# Bus.net
KiCad netlist of a schematic drawn in Altium Designer
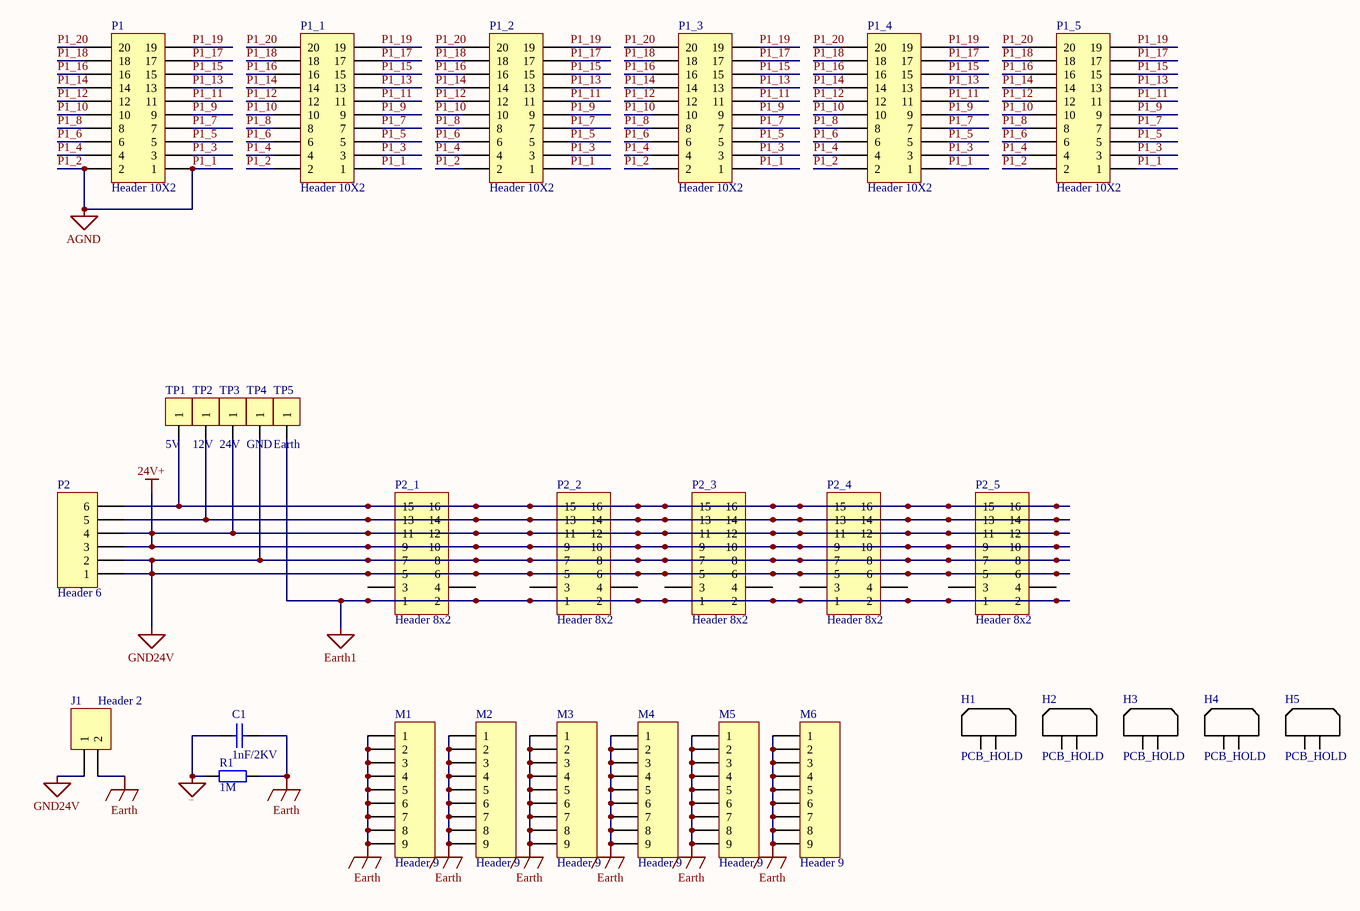
[diagram p0: Bus.SchDoc]

(export (version "E")
  (design (tool "Eeschema 10.0.6"))
  (components
    (comp (ref "C1")
      (value "1nF/2KV")
      (footprint "1206_C")
      (description "Capacitor")
      (libsource (lib "Miscellaneous Devices LC") (part "CC"))
    )
    (comp (ref "H1")
      (value "PCB_HOLD")
      (footprint "PCB_HOLD")
      (fields (field (name "PUBLISHER") "Altium Limited"))
      (libsource (lib "PCB_Project1") (part "PCB_HOLD"))
    )
    (comp (ref "H2")
      (value "PCB_HOLD")
      (footprint "PCB_HOLD")
      (fields (field (name "PUBLISHER") "Altium Limited"))
      (libsource (lib "PCB_Project1") (part "PCB_HOLD"))
    )
    (comp (ref "H3")
      (value "PCB_HOLD")
      (footprint "PCB_HOLD")
      (fields (field (name "PUBLISHER") "Altium Limited"))
      (libsource (lib "PCB_Project1") (part "PCB_HOLD"))
    )
    (comp (ref "H4")
      (value "PCB_HOLD")
      (footprint "PCB_HOLD")
      (fields (field (name "PUBLISHER") "Altium Limited"))
      (libsource (lib "PCB_Project1") (part "PCB_HOLD"))
    )
    (comp (ref "H5")
      (value "PCB_HOLD")
      (footprint "PCB_HOLD")
      (fields (field (name "PUBLISHER") "Altium Limited"))
      (libsource (lib "PCB_Project1") (part "PCB_HOLD"))
    )
    (comp (ref "J1")
      (value "Header 2")
      (footprint "HDR1X2")
      (description "Header, 2-Pin")
      (fields (field (name "PUBLISHER") "Altium Limited"))
      (libsource (lib "Miscellaneous Connectors") (part "Header 2"))
    )
    (comp (ref "M1")
      (value "Header 9")
      (footprint "LK")
      (description "Header, 9-Pin")
      (fields (field (name "PUBLISHER") "Altium Limited"))
      (libsource (lib "Miscellaneous Connectors") (part "Header 9"))
    )
    (comp (ref "M2")
      (value "Header 9")
      (footprint "LK")
      (description "Header, 9-Pin")
      (fields (field (name "PUBLISHER") "Altium Limited"))
      (libsource (lib "Miscellaneous Connectors") (part "Header 9"))
    )
    (comp (ref "M3")
      (value "Header 9")
      (footprint "LK")
      (description "Header, 9-Pin")
      (fields (field (name "PUBLISHER") "Altium Limited"))
      (libsource (lib "Miscellaneous Connectors") (part "Header 9"))
    )
    (comp (ref "M4")
      (value "Header 9")
      (footprint "LK")
      (description "Header, 9-Pin")
      (fields (field (name "PUBLISHER") "Altium Limited"))
      (libsource (lib "Miscellaneous Connectors") (part "Header 9"))
    )
    (comp (ref "M5")
      (value "Header 9")
      (footprint "LK")
      (description "Header, 9-Pin")
      (fields (field (name "PUBLISHER") "Altium Limited"))
      (libsource (lib "Miscellaneous Connectors") (part "Header 9"))
    )
    (comp (ref "M6")
      (value "Header 9")
      (footprint "LK")
      (description "Header, 9-Pin")
      (fields (field (name "PUBLISHER") "Altium Limited"))
      (libsource (lib "Miscellaneous Connectors") (part "Header 9"))
    )
    (comp (ref "P1")
      (value "Header 10X2")
      (footprint "HDR2X10")
      (description "Header, 10-Pin, Dual row")
      (fields (field (name "PUBLISHER") "Altium Limited"))
      (libsource (lib "Miscellaneous Connectors") (part "Header 10X2"))
    )
    (comp (ref "P1_1")
      (value "Header 10X2")
      (footprint "HDR2X10")
      (description "Header, 10-Pin, Dual row")
      (fields (field (name "PUBLISHER") "Altium Limited"))
      (libsource (lib "Miscellaneous Connectors") (part "Header 10X2"))
    )
    (comp (ref "P1_2")
      (value "Header 10X2")
      (footprint "HDR2X10")
      (description "Header, 10-Pin, Dual row")
      (fields (field (name "PUBLISHER") "Altium Limited"))
      (libsource (lib "Miscellaneous Connectors") (part "Header 10X2"))
    )
    (comp (ref "P1_3")
      (value "Header 10X2")
      (footprint "HDR2X10")
      (description "Header, 10-Pin, Dual row")
      (fields (field (name "PUBLISHER") "Altium Limited"))
      (libsource (lib "Miscellaneous Connectors") (part "Header 10X2"))
    )
    (comp (ref "P1_4")
      (value "Header 10X2")
      (footprint "HDR2X10")
      (description "Header, 10-Pin, Dual row")
      (fields (field (name "PUBLISHER") "Altium Limited"))
      (libsource (lib "Miscellaneous Connectors") (part "Header 10X2"))
    )
    (comp (ref "P1_5")
      (value "Header 10X2")
      (footprint "HDR2X10")
      (description "Header, 10-Pin, Dual row")
      (fields (field (name "PUBLISHER") "Altium Limited"))
      (libsource (lib "Miscellaneous Connectors") (part "Header 10X2"))
    )
    (comp (ref "P2")
      (value "Header 6")
      (footprint "15EDG-6-R")
      (description "Header, 6-Pin")
      (fields (field (name "PUBLISHER") "Altium Limited"))
      (libsource (lib "Miscellaneous Connectors") (part "Header 6"))
    )
    (comp (ref "P2_1")
      (value "Header 8x2")
      (footprint "HDR2X8")
      (description "Header, 8-Pin, Dual row")
      (fields (field (name "PUBLISHER") "Altium Limited"))
      (libsource (lib "Miscellaneous Connectors") (part "Header 8X2"))
    )
    (comp (ref "P2_2")
      (value "Header 8x2")
      (footprint "HDR2X8")
      (description "Header, 8-Pin, Dual row")
      (fields (field (name "PUBLISHER") "Altium Limited"))
      (libsource (lib "Miscellaneous Connectors") (part "Header 8X2"))
    )
    (comp (ref "P2_3")
      (value "Header 8x2")
      (footprint "HDR2X8")
      (description "Header, 8-Pin, Dual row")
      (fields (field (name "PUBLISHER") "Altium Limited"))
      (libsource (lib "Miscellaneous Connectors") (part "Header 8X2"))
    )
    (comp (ref "P2_4")
      (value "Header 8x2")
      (footprint "HDR2X8")
      (description "Header, 8-Pin, Dual row")
      (fields (field (name "PUBLISHER") "Altium Limited"))
      (libsource (lib "Miscellaneous Connectors") (part "Header 8X2"))
    )
    (comp (ref "P2_5")
      (value "Header 8x2")
      (footprint "HDR2X8")
      (description "Header, 8-Pin, Dual row")
      (fields (field (name "PUBLISHER") "Altium Limited"))
      (libsource (lib "Miscellaneous Connectors") (part "Header 8X2"))
    )
    (comp (ref "R1")
      (value "1M")
      (footprint "1206_R")
      (description "Resistor")
      (fields (field (name "PUBLISHER") "Altium Limited"))
      (libsource (lib "Miscellaneous Devices LC") (part "Res2"))
    )
    (comp (ref "TP1")
      (value "5V")
      (footprint "TP")
      (description "TP")
      (fields (field (name "PUBLISHER") "Altium Limited"))
      (libsource (lib "GW") (part "TP"))
    )
    (comp (ref "TP2")
      (value "12V")
      (footprint "TP")
      (description "TP")
      (fields (field (name "PUBLISHER") "Altium Limited"))
      (libsource (lib "GW") (part "TP"))
    )
    (comp (ref "TP3")
      (value "24V")
      (footprint "TP")
      (description "TP")
      (fields (field (name "PUBLISHER") "Altium Limited"))
      (libsource (lib "GW") (part "TP"))
    )
    (comp (ref "TP4")
      (value "GND")
      (footprint "TP")
      (description "TP")
      (fields (field (name "PUBLISHER") "Altium Limited"))
      (libsource (lib "GW") (part "TP"))
    )
    (comp (ref "TP5")
      (value "Earth")
      (footprint "TP")
      (description "TP")
      (fields (field (name "PUBLISHER") "Altium Limited"))
      (libsource (lib "GW") (part "TP"))
    )
  )
  (nets
    (net (code "1") (name "/P1_3") (class "Default")
      (node (ref "P1") (pin "3") (pinfunction "3_3") (pintype "passive"))
      (node (ref "P1_1") (pin "3") (pinfunction "3_3") (pintype "passive"))
      (node (ref "P1_2") (pin "3") (pinfunction "3_3") (pintype "passive"))
      (node (ref "P1_3") (pin "3") (pinfunction "3_3") (pintype "passive"))
      (node (ref "P1_4") (pin "3") (pinfunction "3_3") (pintype "passive"))
      (node (ref "P1_5") (pin "3") (pinfunction "3_3") (pintype "passive"))
    )
    (net (code "2") (name "/P1_4") (class "Default")
      (node (ref "P1") (pin "4") (pinfunction "4_4") (pintype "passive"))
      (node (ref "P1_1") (pin "4") (pinfunction "4_4") (pintype "passive"))
      (node (ref "P1_2") (pin "4") (pinfunction "4_4") (pintype "passive"))
      (node (ref "P1_3") (pin "4") (pinfunction "4_4") (pintype "passive"))
      (node (ref "P1_4") (pin "4") (pinfunction "4_4") (pintype "passive"))
      (node (ref "P1_5") (pin "4") (pinfunction "4_4") (pintype "passive"))
    )
    (net (code "3") (name "/P1_5") (class "Default")
      (node (ref "P1") (pin "5") (pinfunction "5_5") (pintype "passive"))
      (node (ref "P1_1") (pin "5") (pinfunction "5_5") (pintype "passive"))
      (node (ref "P1_2") (pin "5") (pinfunction "5_5") (pintype "passive"))
      (node (ref "P1_3") (pin "5") (pinfunction "5_5") (pintype "passive"))
      (node (ref "P1_4") (pin "5") (pinfunction "5_5") (pintype "passive"))
      (node (ref "P1_5") (pin "5") (pinfunction "5_5") (pintype "passive"))
    )
    (net (code "4") (name "/P1_6") (class "Default")
      (node (ref "P1") (pin "6") (pinfunction "6_6") (pintype "passive"))
      (node (ref "P1_1") (pin "6") (pinfunction "6_6") (pintype "passive"))
      (node (ref "P1_2") (pin "6") (pinfunction "6_6") (pintype "passive"))
      (node (ref "P1_3") (pin "6") (pinfunction "6_6") (pintype "passive"))
      (node (ref "P1_4") (pin "6") (pinfunction "6_6") (pintype "passive"))
      (node (ref "P1_5") (pin "6") (pinfunction "6_6") (pintype "passive"))
    )
    (net (code "5") (name "/P1_7") (class "Default")
      (node (ref "P1") (pin "7") (pinfunction "7_7") (pintype "passive"))
      (node (ref "P1_1") (pin "7") (pinfunction "7_7") (pintype "passive"))
      (node (ref "P1_2") (pin "7") (pinfunction "7_7") (pintype "passive"))
      (node (ref "P1_3") (pin "7") (pinfunction "7_7") (pintype "passive"))
      (node (ref "P1_4") (pin "7") (pinfunction "7_7") (pintype "passive"))
      (node (ref "P1_5") (pin "7") (pinfunction "7_7") (pintype "passive"))
    )
    (net (code "6") (name "/P1_8") (class "Default")
      (node (ref "P1") (pin "8") (pinfunction "8_8") (pintype "passive"))
      (node (ref "P1_1") (pin "8") (pinfunction "8_8") (pintype "passive"))
      (node (ref "P1_2") (pin "8") (pinfunction "8_8") (pintype "passive"))
      (node (ref "P1_3") (pin "8") (pinfunction "8_8") (pintype "passive"))
      (node (ref "P1_4") (pin "8") (pinfunction "8_8") (pintype "passive"))
      (node (ref "P1_5") (pin "8") (pinfunction "8_8") (pintype "passive"))
    )
    (net (code "7") (name "/P1_9") (class "Default")
      (node (ref "P1") (pin "9") (pinfunction "9_9") (pintype "passive"))
      (node (ref "P1_1") (pin "9") (pinfunction "9_9") (pintype "passive"))
      (node (ref "P1_2") (pin "9") (pinfunction "9_9") (pintype "passive"))
      (node (ref "P1_3") (pin "9") (pinfunction "9_9") (pintype "passive"))
      (node (ref "P1_4") (pin "9") (pinfunction "9_9") (pintype "passive"))
      (node (ref "P1_5") (pin "9") (pinfunction "9_9") (pintype "passive"))
    )
    (net (code "8") (name "/P1_10") (class "Default")
      (node (ref "P1") (pin "10") (pinfunction "10_10") (pintype "passive"))
      (node (ref "P1_1") (pin "10") (pinfunction "10_10") (pintype "passive"))
      (node (ref "P1_2") (pin "10") (pinfunction "10_10") (pintype "passive"))
      (node (ref "P1_3") (pin "10") (pinfunction "10_10") (pintype "passive"))
      (node (ref "P1_4") (pin "10") (pinfunction "10_10") (pintype "passive"))
      (node (ref "P1_5") (pin "10") (pinfunction "10_10") (pintype "passive"))
    )
    (net (code "9") (name "/P1_11") (class "Default")
      (node (ref "P1") (pin "11") (pinfunction "11_11") (pintype "passive"))
      (node (ref "P1_1") (pin "11") (pinfunction "11_11") (pintype "passive"))
      (node (ref "P1_2") (pin "11") (pinfunction "11_11") (pintype "passive"))
      (node (ref "P1_3") (pin "11") (pinfunction "11_11") (pintype "passive"))
      (node (ref "P1_4") (pin "11") (pinfunction "11_11") (pintype "passive"))
      (node (ref "P1_5") (pin "11") (pinfunction "11_11") (pintype "passive"))
    )
    (net (code "10") (name "/P1_12") (class "Default")
      (node (ref "P1") (pin "12") (pinfunction "12_12") (pintype "passive"))
      (node (ref "P1_1") (pin "12") (pinfunction "12_12") (pintype "passive"))
      (node (ref "P1_2") (pin "12") (pinfunction "12_12") (pintype "passive"))
      (node (ref "P1_3") (pin "12") (pinfunction "12_12") (pintype "passive"))
      (node (ref "P1_4") (pin "12") (pinfunction "12_12") (pintype "passive"))
      (node (ref "P1_5") (pin "12") (pinfunction "12_12") (pintype "passive"))
    )
    (net (code "11") (name "/P1_13") (class "Default")
      (node (ref "P1") (pin "13") (pinfunction "13_13") (pintype "passive"))
      (node (ref "P1_1") (pin "13") (pinfunction "13_13") (pintype "passive"))
      (node (ref "P1_2") (pin "13") (pinfunction "13_13") (pintype "passive"))
      (node (ref "P1_3") (pin "13") (pinfunction "13_13") (pintype "passive"))
      (node (ref "P1_4") (pin "13") (pinfunction "13_13") (pintype "passive"))
      (node (ref "P1_5") (pin "13") (pinfunction "13_13") (pintype "passive"))
    )
    (net (code "12") (name "/P1_14") (class "Default")
      (node (ref "P1") (pin "14") (pinfunction "14_14") (pintype "passive"))
      (node (ref "P1_1") (pin "14") (pinfunction "14_14") (pintype "passive"))
      (node (ref "P1_2") (pin "14") (pinfunction "14_14") (pintype "passive"))
      (node (ref "P1_3") (pin "14") (pinfunction "14_14") (pintype "passive"))
      (node (ref "P1_4") (pin "14") (pinfunction "14_14") (pintype "passive"))
      (node (ref "P1_5") (pin "14") (pinfunction "14_14") (pintype "passive"))
    )
    (net (code "13") (name "/P1_15") (class "Default")
      (node (ref "P1") (pin "15") (pinfunction "15_15") (pintype "passive"))
      (node (ref "P1_1") (pin "15") (pinfunction "15_15") (pintype "passive"))
      (node (ref "P1_2") (pin "15") (pinfunction "15_15") (pintype "passive"))
      (node (ref "P1_3") (pin "15") (pinfunction "15_15") (pintype "passive"))
      (node (ref "P1_4") (pin "15") (pinfunction "15_15") (pintype "passive"))
      (node (ref "P1_5") (pin "15") (pinfunction "15_15") (pintype "passive"))
    )
    (net (code "14") (name "/P1_16") (class "Default")
      (node (ref "P1") (pin "16") (pinfunction "16_16") (pintype "passive"))
      (node (ref "P1_1") (pin "16") (pinfunction "16_16") (pintype "passive"))
      (node (ref "P1_2") (pin "16") (pinfunction "16_16") (pintype "passive"))
      (node (ref "P1_3") (pin "16") (pinfunction "16_16") (pintype "passive"))
      (node (ref "P1_4") (pin "16") (pinfunction "16_16") (pintype "passive"))
      (node (ref "P1_5") (pin "16") (pinfunction "16_16") (pintype "passive"))
    )
    (net (code "15") (name "/P1_17") (class "Default")
      (node (ref "P1") (pin "17") (pinfunction "17_17") (pintype "passive"))
      (node (ref "P1_1") (pin "17") (pinfunction "17_17") (pintype "passive"))
      (node (ref "P1_2") (pin "17") (pinfunction "17_17") (pintype "passive"))
      (node (ref "P1_3") (pin "17") (pinfunction "17_17") (pintype "passive"))
      (node (ref "P1_4") (pin "17") (pinfunction "17_17") (pintype "passive"))
      (node (ref "P1_5") (pin "17") (pinfunction "17_17") (pintype "passive"))
    )
    (net (code "16") (name "/P1_18") (class "Default")
      (node (ref "P1") (pin "18") (pinfunction "18_18") (pintype "passive"))
      (node (ref "P1_1") (pin "18") (pinfunction "18_18") (pintype "passive"))
      (node (ref "P1_2") (pin "18") (pinfunction "18_18") (pintype "passive"))
      (node (ref "P1_3") (pin "18") (pinfunction "18_18") (pintype "passive"))
      (node (ref "P1_4") (pin "18") (pinfunction "18_18") (pintype "passive"))
      (node (ref "P1_5") (pin "18") (pinfunction "18_18") (pintype "passive"))
    )
    (net (code "17") (name "/P1_19") (class "Default")
      (node (ref "P1") (pin "19") (pinfunction "19_19") (pintype "passive"))
      (node (ref "P1_1") (pin "19") (pinfunction "19_19") (pintype "passive"))
      (node (ref "P1_2") (pin "19") (pinfunction "19_19") (pintype "passive"))
      (node (ref "P1_3") (pin "19") (pinfunction "19_19") (pintype "passive"))
      (node (ref "P1_4") (pin "19") (pinfunction "19_19") (pintype "passive"))
      (node (ref "P1_5") (pin "19") (pinfunction "19_19") (pintype "passive"))
    )
    (net (code "18") (name "/P1_20") (class "Default")
      (node (ref "P1") (pin "20") (pinfunction "20_20") (pintype "passive"))
      (node (ref "P1_1") (pin "20") (pinfunction "20_20") (pintype "passive"))
      (node (ref "P1_2") (pin "20") (pinfunction "20_20") (pintype "passive"))
      (node (ref "P1_3") (pin "20") (pinfunction "20_20") (pintype "passive"))
      (node (ref "P1_4") (pin "20") (pinfunction "20_20") (pintype "passive"))
      (node (ref "P1_5") (pin "20") (pinfunction "20_20") (pintype "passive"))
    )
    (net (code "19") (name "24V+") (class "Default")
      (node (ref "P2") (pin "3") (pinfunction "3_3") (pintype "passive"))
      (node (ref "P2") (pin "4") (pinfunction "4_4") (pintype "passive"))
      (node (ref "P2_1") (pin "10") (pinfunction "10_10") (pintype "passive"))
      (node (ref "P2_1") (pin "11") (pinfunction "11_11") (pintype "passive"))
      (node (ref "P2_1") (pin "12") (pinfunction "12_12") (pintype "passive"))
      (node (ref "P2_1") (pin "9") (pinfunction "9_9") (pintype "passive"))
      (node (ref "P2_2") (pin "10") (pinfunction "10_10") (pintype "passive"))
      (node (ref "P2_2") (pin "11") (pinfunction "11_11") (pintype "passive"))
      (node (ref "P2_2") (pin "12") (pinfunction "12_12") (pintype "passive"))
      (node (ref "P2_2") (pin "9") (pinfunction "9_9") (pintype "passive"))
      (node (ref "P2_3") (pin "10") (pinfunction "10_10") (pintype "passive"))
      (node (ref "P2_3") (pin "11") (pinfunction "11_11") (pintype "passive"))
      (node (ref "P2_3") (pin "12") (pinfunction "12_12") (pintype "passive"))
      (node (ref "P2_3") (pin "9") (pinfunction "9_9") (pintype "passive"))
      (node (ref "P2_4") (pin "10") (pinfunction "10_10") (pintype "passive"))
      (node (ref "P2_4") (pin "11") (pinfunction "11_11") (pintype "passive"))
      (node (ref "P2_4") (pin "12") (pinfunction "12_12") (pintype "passive"))
      (node (ref "P2_4") (pin "9") (pinfunction "9_9") (pintype "passive"))
      (node (ref "P2_5") (pin "10") (pinfunction "10_10") (pintype "passive"))
      (node (ref "P2_5") (pin "11") (pinfunction "11_11") (pintype "passive"))
      (node (ref "P2_5") (pin "12") (pinfunction "12_12") (pintype "passive"))
      (node (ref "P2_5") (pin "9") (pinfunction "9_9") (pintype "passive"))
      (node (ref "TP3") (pin "1") (pinfunction "1_1") (pintype "passive"))
    )
    (net (code "20") (name "AGND") (class "Default")
      (node (ref "P1") (pin "1") (pinfunction "1_1") (pintype "passive"))
      (node (ref "P1") (pin "2") (pinfunction "2_2") (pintype "passive"))
      (node (ref "P1_1") (pin "1") (pinfunction "1_1") (pintype "passive"))
      (node (ref "P1_1") (pin "2") (pinfunction "2_2") (pintype "passive"))
      (node (ref "P1_2") (pin "1") (pinfunction "1_1") (pintype "passive"))
      (node (ref "P1_2") (pin "2") (pinfunction "2_2") (pintype "passive"))
      (node (ref "P1_3") (pin "1") (pinfunction "1_1") (pintype "passive"))
      (node (ref "P1_3") (pin "2") (pinfunction "2_2") (pintype "passive"))
      (node (ref "P1_4") (pin "1") (pinfunction "1_1") (pintype "passive"))
      (node (ref "P1_4") (pin "2") (pinfunction "2_2") (pintype "passive"))
      (node (ref "P1_5") (pin "1") (pinfunction "1_1") (pintype "passive"))
      (node (ref "P1_5") (pin "2") (pinfunction "2_2") (pintype "passive"))
    )
    (net (code "21") (name "Earth") (class "Default")
      (node (ref "C1") (pin "1") (pinfunction "1_1") (pintype "passive"))
      (node (ref "J1") (pin "2") (pinfunction "2_2") (pintype "passive"))
      (node (ref "M1") (pin "1") (pinfunction "1_1") (pintype "passive"))
      (node (ref "M1") (pin "2") (pinfunction "2_2") (pintype "passive"))
      (node (ref "M1") (pin "3") (pinfunction "3_3") (pintype "passive"))
      (node (ref "M1") (pin "4") (pinfunction "4_4") (pintype "passive"))
      (node (ref "M1") (pin "5") (pinfunction "5_5") (pintype "passive"))
      (node (ref "M1") (pin "6") (pinfunction "6_6") (pintype "passive"))
      (node (ref "M1") (pin "7") (pinfunction "7_7") (pintype "passive"))
      (node (ref "M1") (pin "8") (pinfunction "8_8") (pintype "passive"))
      (node (ref "M1") (pin "9") (pinfunction "9_9") (pintype "passive"))
      (node (ref "M2") (pin "1") (pinfunction "1_1") (pintype "passive"))
      (node (ref "M2") (pin "2") (pinfunction "2_2") (pintype "passive"))
      (node (ref "M2") (pin "3") (pinfunction "3_3") (pintype "passive"))
      (node (ref "M2") (pin "4") (pinfunction "4_4") (pintype "passive"))
      (node (ref "M2") (pin "5") (pinfunction "5_5") (pintype "passive"))
      (node (ref "M2") (pin "6") (pinfunction "6_6") (pintype "passive"))
      (node (ref "M2") (pin "7") (pinfunction "7_7") (pintype "passive"))
      (node (ref "M2") (pin "8") (pinfunction "8_8") (pintype "passive"))
      (node (ref "M2") (pin "9") (pinfunction "9_9") (pintype "passive"))
      (node (ref "M3") (pin "1") (pinfunction "1_1") (pintype "passive"))
      (node (ref "M3") (pin "2") (pinfunction "2_2") (pintype "passive"))
      (node (ref "M3") (pin "3") (pinfunction "3_3") (pintype "passive"))
      (node (ref "M3") (pin "4") (pinfunction "4_4") (pintype "passive"))
      (node (ref "M3") (pin "5") (pinfunction "5_5") (pintype "passive"))
      (node (ref "M3") (pin "6") (pinfunction "6_6") (pintype "passive"))
      (node (ref "M3") (pin "7") (pinfunction "7_7") (pintype "passive"))
      (node (ref "M3") (pin "8") (pinfunction "8_8") (pintype "passive"))
      (node (ref "M3") (pin "9") (pinfunction "9_9") (pintype "passive"))
      (node (ref "M4") (pin "1") (pinfunction "1_1") (pintype "passive"))
      (node (ref "M4") (pin "2") (pinfunction "2_2") (pintype "passive"))
      (node (ref "M4") (pin "3") (pinfunction "3_3") (pintype "passive"))
      (node (ref "M4") (pin "4") (pinfunction "4_4") (pintype "passive"))
      (node (ref "M4") (pin "5") (pinfunction "5_5") (pintype "passive"))
      (node (ref "M4") (pin "6") (pinfunction "6_6") (pintype "passive"))
      (node (ref "M4") (pin "7") (pinfunction "7_7") (pintype "passive"))
      (node (ref "M4") (pin "8") (pinfunction "8_8") (pintype "passive"))
      (node (ref "M4") (pin "9") (pinfunction "9_9") (pintype "passive"))
      (node (ref "M5") (pin "1") (pinfunction "1_1") (pintype "passive"))
      (node (ref "M5") (pin "2") (pinfunction "2_2") (pintype "passive"))
      (node (ref "M5") (pin "3") (pinfunction "3_3") (pintype "passive"))
      (node (ref "M5") (pin "4") (pinfunction "4_4") (pintype "passive"))
      (node (ref "M5") (pin "5") (pinfunction "5_5") (pintype "passive"))
      (node (ref "M5") (pin "6") (pinfunction "6_6") (pintype "passive"))
      (node (ref "M5") (pin "7") (pinfunction "7_7") (pintype "passive"))
      (node (ref "M5") (pin "8") (pinfunction "8_8") (pintype "passive"))
      (node (ref "M5") (pin "9") (pinfunction "9_9") (pintype "passive"))
      (node (ref "M6") (pin "1") (pinfunction "1_1") (pintype "passive"))
      (node (ref "M6") (pin "2") (pinfunction "2_2") (pintype "passive"))
      (node (ref "M6") (pin "3") (pinfunction "3_3") (pintype "passive"))
      (node (ref "M6") (pin "4") (pinfunction "4_4") (pintype "passive"))
      (node (ref "M6") (pin "5") (pinfunction "5_5") (pintype "passive"))
      (node (ref "M6") (pin "6") (pinfunction "6_6") (pintype "passive"))
      (node (ref "M6") (pin "7") (pinfunction "7_7") (pintype "passive"))
      (node (ref "M6") (pin "8") (pinfunction "8_8") (pintype "passive"))
      (node (ref "M6") (pin "9") (pinfunction "9_9") (pintype "passive"))
      (node (ref "R1") (pin "2") (pinfunction "2_2") (pintype "passive"))
    )
    (net (code "22") (name "Earth1") (class "Default")
      (node (ref "C1") (pin "2") (pinfunction "2_2") (pintype "passive"))
      (node (ref "P2_1") (pin "1") (pinfunction "1_1") (pintype "passive"))
      (node (ref "P2_1") (pin "2") (pinfunction "2_2") (pintype "passive"))
      (node (ref "P2_2") (pin "1") (pinfunction "1_1") (pintype "passive"))
      (node (ref "P2_2") (pin "2") (pinfunction "2_2") (pintype "passive"))
      (node (ref "P2_3") (pin "1") (pinfunction "1_1") (pintype "passive"))
      (node (ref "P2_3") (pin "2") (pinfunction "2_2") (pintype "passive"))
      (node (ref "P2_4") (pin "1") (pinfunction "1_1") (pintype "passive"))
      (node (ref "P2_4") (pin "2") (pinfunction "2_2") (pintype "passive"))
      (node (ref "P2_5") (pin "1") (pinfunction "1_1") (pintype "passive"))
      (node (ref "P2_5") (pin "2") (pinfunction "2_2") (pintype "passive"))
      (node (ref "R1") (pin "1") (pinfunction "1_1") (pintype "passive"))
      (node (ref "TP5") (pin "1") (pinfunction "1_1") (pintype "passive"))
    )
    (net (code "23") (name "GND24V") (class "Default")
      (node (ref "J1") (pin "1") (pinfunction "1_1") (pintype "passive"))
      (node (ref "P2") (pin "1") (pinfunction "1_1") (pintype "passive"))
      (node (ref "P2") (pin "2") (pinfunction "2_2") (pintype "passive"))
      (node (ref "P2_1") (pin "5") (pinfunction "5_5") (pintype "passive"))
      (node (ref "P2_1") (pin "6") (pinfunction "6_6") (pintype "passive"))
      (node (ref "P2_1") (pin "7") (pinfunction "7_7") (pintype "passive"))
      (node (ref "P2_1") (pin "8") (pinfunction "8_8") (pintype "passive"))
      (node (ref "P2_2") (pin "5") (pinfunction "5_5") (pintype "passive"))
      (node (ref "P2_2") (pin "6") (pinfunction "6_6") (pintype "passive"))
      (node (ref "P2_2") (pin "7") (pinfunction "7_7") (pintype "passive"))
      (node (ref "P2_2") (pin "8") (pinfunction "8_8") (pintype "passive"))
      (node (ref "P2_3") (pin "5") (pinfunction "5_5") (pintype "passive"))
      (node (ref "P2_3") (pin "6") (pinfunction "6_6") (pintype "passive"))
      (node (ref "P2_3") (pin "7") (pinfunction "7_7") (pintype "passive"))
      (node (ref "P2_3") (pin "8") (pinfunction "8_8") (pintype "passive"))
      (node (ref "P2_4") (pin "5") (pinfunction "5_5") (pintype "passive"))
      (node (ref "P2_4") (pin "6") (pinfunction "6_6") (pintype "passive"))
      (node (ref "P2_4") (pin "7") (pinfunction "7_7") (pintype "passive"))
      (node (ref "P2_4") (pin "8") (pinfunction "8_8") (pintype "passive"))
      (node (ref "P2_5") (pin "5") (pinfunction "5_5") (pintype "passive"))
      (node (ref "P2_5") (pin "6") (pinfunction "6_6") (pintype "passive"))
      (node (ref "P2_5") (pin "7") (pinfunction "7_7") (pintype "passive"))
      (node (ref "P2_5") (pin "8") (pinfunction "8_8") (pintype "passive"))
      (node (ref "TP4") (pin "1") (pinfunction "1_1") (pintype "passive"))
    )
    (net (code "24") (name "Net-(P2-Pad5)") (class "Default")
      (node (ref "P2") (pin "5") (pinfunction "5_5") (pintype "passive"))
      (node (ref "P2_1") (pin "13") (pinfunction "13_13") (pintype "passive"))
      (node (ref "P2_1") (pin "14") (pinfunction "14_14") (pintype "passive"))
      (node (ref "P2_2") (pin "13") (pinfunction "13_13") (pintype "passive"))
      (node (ref "P2_2") (pin "14") (pinfunction "14_14") (pintype "passive"))
      (node (ref "P2_3") (pin "13") (pinfunction "13_13") (pintype "passive"))
      (node (ref "P2_3") (pin "14") (pinfunction "14_14") (pintype "passive"))
      (node (ref "P2_4") (pin "13") (pinfunction "13_13") (pintype "passive"))
      (node (ref "P2_4") (pin "14") (pinfunction "14_14") (pintype "passive"))
      (node (ref "P2_5") (pin "13") (pinfunction "13_13") (pintype "passive"))
      (node (ref "P2_5") (pin "14") (pinfunction "14_14") (pintype "passive"))
      (node (ref "TP2") (pin "1") (pinfunction "1_1") (pintype "passive"))
    )
    (net (code "25") (name "Net-(P2-Pad6)") (class "Default")
      (node (ref "P2") (pin "6") (pinfunction "6_6") (pintype "passive"))
      (node (ref "P2_1") (pin "15") (pinfunction "15_15") (pintype "passive"))
      (node (ref "P2_1") (pin "16") (pinfunction "16_16") (pintype "passive"))
      (node (ref "P2_2") (pin "15") (pinfunction "15_15") (pintype "passive"))
      (node (ref "P2_2") (pin "16") (pinfunction "16_16") (pintype "passive"))
      (node (ref "P2_3") (pin "15") (pinfunction "15_15") (pintype "passive"))
      (node (ref "P2_3") (pin "16") (pinfunction "16_16") (pintype "passive"))
      (node (ref "P2_4") (pin "15") (pinfunction "15_15") (pintype "passive"))
      (node (ref "P2_4") (pin "16") (pinfunction "16_16") (pintype "passive"))
      (node (ref "P2_5") (pin "15") (pinfunction "15_15") (pintype "passive"))
      (node (ref "P2_5") (pin "16") (pinfunction "16_16") (pintype "passive"))
      (node (ref "TP1") (pin "1") (pinfunction "1_1") (pintype "passive"))
    )
    (net (code "26") (name "unconnected-(P2_1-Pad3)") (class "Default")
      (node (ref "P2_1") (pin "3") (pinfunction "3_3") (pintype "passive"))
    )
    (net (code "27") (name "unconnected-(P2_1-Pad4)") (class "Default")
      (node (ref "P2_1") (pin "4") (pinfunction "4_4") (pintype "passive"))
    )
    (net (code "28") (name "unconnected-(P2_2-Pad3)") (class "Default")
      (node (ref "P2_2") (pin "3") (pinfunction "3_3") (pintype "passive"))
    )
    (net (code "29") (name "unconnected-(P2_2-Pad4)") (class "Default")
      (node (ref "P2_2") (pin "4") (pinfunction "4_4") (pintype "passive"))
    )
    (net (code "30") (name "unconnected-(P2_3-Pad3)") (class "Default")
      (node (ref "P2_3") (pin "3") (pinfunction "3_3") (pintype "passive"))
    )
    (net (code "31") (name "unconnected-(P2_3-Pad4)") (class "Default")
      (node (ref "P2_3") (pin "4") (pinfunction "4_4") (pintype "passive"))
    )
    (net (code "32") (name "unconnected-(P2_4-Pad3)") (class "Default")
      (node (ref "P2_4") (pin "3") (pinfunction "3_3") (pintype "passive"))
    )
    (net (code "33") (name "unconnected-(P2_4-Pad4)") (class "Default")
      (node (ref "P2_4") (pin "4") (pinfunction "4_4") (pintype "passive"))
    )
    (net (code "34") (name "unconnected-(P2_5-Pad3)") (class "Default")
      (node (ref "P2_5") (pin "3") (pinfunction "3_3") (pintype "passive"))
    )
    (net (code "35") (name "unconnected-(P2_5-Pad4)") (class "Default")
      (node (ref "P2_5") (pin "4") (pinfunction "4_4") (pintype "passive"))
    )
  )
)
